# Nusbio_smd.net
KiCad netlist of a schematic drawn in EAGLE
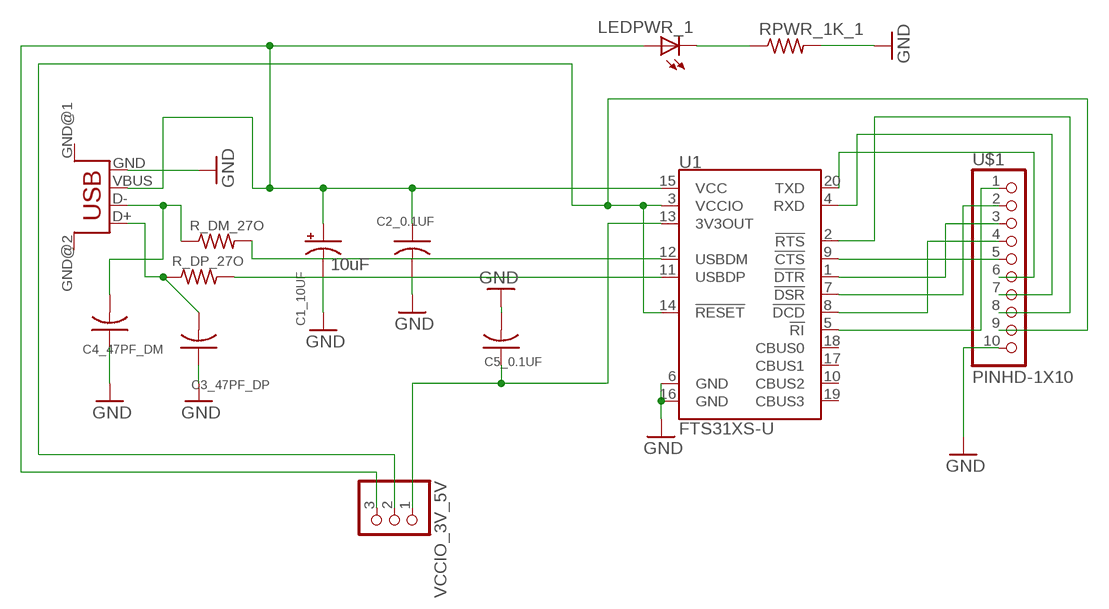
[diagram p0: schematic, sheet 1]

(export (version "E")
  (design (tool "Eeschema 10.0.6"))
  (components
    (comp (ref "C1_10UF")
      (value "10uF")
      (footprint "eagle-import:EIA3216")
      (libsource (lib "eagle-import") (part "10UF-16V-10%(TANT)"))
    )
    (comp (ref "C2_0.1UF")
      (value "C-USC1206")
      (footprint "eagle-import:C1206")
      (libsource (lib "eagle-import") (part "C-USC1206"))
    )
    (comp (ref "C3_47PF_DP")
      (value "C-USC1206")
      (footprint "eagle-import:C1206")
      (libsource (lib "eagle-import") (part "C-USC1206"))
    )
    (comp (ref "C4_47PF_DM")
      (value "C-USC1206")
      (footprint "eagle-import:C1206")
      (libsource (lib "eagle-import") (part "C-USC1206"))
    )
    (comp (ref "C5_0.1UF")
      (value "C-USC1206")
      (footprint "eagle-import:C1206")
      (libsource (lib "eagle-import") (part "C-USC1206"))
    )
    (comp (ref "LEDPWR_1")
      (value "LEDCHIPLED_0805")
      (footprint "eagle-import:CHIPLED_0805")
      (libsource (lib "eagle-import") (part "LEDCHIPLED_0805"))
    )
    (comp (ref "RPWR_1K_1")
      (value "R-US_R0805")
      (footprint "eagle-import:R0805")
      (libsource (lib "eagle-import") (part "R-US_R0805"))
    )
    (comp (ref "R_DM_27O")
      (value "R-US_R0805")
      (footprint "eagle-import:R0805")
      (libsource (lib "eagle-import") (part "R-US_R0805"))
    )
    (comp (ref "R_DP_27O")
      (value "R-US_R0805")
      (footprint "eagle-import:R0805")
      (libsource (lib "eagle-import") (part "R-US_R0805"))
    )
    (comp (ref "U$1")
      (value "PINHD-1X10")
      (footprint "eagle-import:1X10-BIG")
      (libsource (lib "eagle-import") (part "PINHD-1X10"))
    )
    (comp (ref "U1")
      (value "FTS31XS-U")
      (footprint "eagle-import:SSOP20_L")
      (libsource (lib "eagle-import") (part "FT231XS"))
    )
    (comp (ref "USB_FEMALE")
      (value "USB")
      (footprint "eagle-import:USB-FEMALE-A-PTH")
      (libsource (lib "eagle-import") (part "USB"))
    )
    (comp (ref "VCCIO_3V_5V")
      (value "PINHD-1X3")
      (footprint "eagle-import:1X03")
      (libsource (lib "eagle-import") (part "PINHD-1X3"))
    )
  )
  (nets
    (net (code "1") (name "GND") (class "Default")
      (node (ref "C1_10UF") (pin "C") (pinfunction "-_C") (pintype "passive"))
      (node (ref "C2_0.1UF") (pin "2") (pinfunction "2_2") (pintype "passive"))
      (node (ref "C3_47PF_DP") (pin "1") (pinfunction "1_1") (pintype "passive"))
      (node (ref "C4_47PF_DM") (pin "1") (pinfunction "1_1") (pintype "passive"))
      (node (ref "C5_0.1UF") (pin "2") (pinfunction "2_2") (pintype "passive"))
      (node (ref "RPWR_1K_1") (pin "2") (pinfunction "2_2") (pintype "passive"))
      (node (ref "U$1") (pin "10") (pinfunction "10_10") (pintype "passive"))
      (node (ref "U1") (pin "16") (pinfunction "GND_16") (pintype "bidirectional"))
      (node (ref "U1") (pin "6") (pinfunction "GND_6") (pintype "bidirectional"))
      (node (ref "USB_FEMALE") (pin "GND") (pinfunction "GND_GND") (pintype "bidirectional"))
    )
    (net (code "2") (name "Net-(C1_10UF-+)") (class "Default")
      (node (ref "C1_10UF") (pin "A") (pinfunction "+_A") (pintype "passive"))
      (node (ref "C2_0.1UF") (pin "1") (pinfunction "1_1") (pintype "passive"))
      (node (ref "LEDPWR_1") (pin "A") (pinfunction "A_A") (pintype "passive"))
      (node (ref "U1") (pin "15") (pinfunction "VCC_15") (pintype "bidirectional"))
      (node (ref "USB_FEMALE") (pin "VBUS") (pinfunction "VBUS_VBUS") (pintype "bidirectional"))
      (node (ref "VCCIO_3V_5V") (pin "3") (pinfunction "3_3") (pintype "passive"))
    )
    (net (code "3") (name "Net-(C3_47PF_DP-Pad2)") (class "Default")
      (node (ref "C3_47PF_DP") (pin "2") (pinfunction "2_2") (pintype "passive"))
      (node (ref "R_DP_27O") (pin "1") (pinfunction "1_1") (pintype "passive"))
      (node (ref "USB_FEMALE") (pin "D+") (pinfunction "D+_D+") (pintype "bidirectional"))
    )
    (net (code "4") (name "Net-(C4_47PF_DM-Pad2)") (class "Default")
      (node (ref "C4_47PF_DM") (pin "2") (pinfunction "2_2") (pintype "passive"))
      (node (ref "R_DM_27O") (pin "1") (pinfunction "1_1") (pintype "passive"))
      (node (ref "USB_FEMALE") (pin "D-") (pinfunction "D-_D-") (pintype "bidirectional"))
    )
    (net (code "5") (name "Net-(LEDPWR_1-PadC)") (class "Default")
      (node (ref "LEDPWR_1") (pin "C") (pinfunction "C_C") (pintype "passive"))
      (node (ref "RPWR_1K_1") (pin "1") (pinfunction "1_1") (pintype "passive"))
    )
    (net (code "6") (name "Net-(U1-3V3OUT)") (class "Default")
      (node (ref "C5_0.1UF") (pin "1") (pinfunction "1_1") (pintype "passive"))
      (node (ref "U1") (pin "13") (pinfunction "3V3OUT_13") (pintype "bidirectional"))
      (node (ref "VCCIO_3V_5V") (pin "1") (pinfunction "1_1") (pintype "passive"))
    )
    (net (code "7") (name "Net-(U1-RXD)") (class "Default")
      (node (ref "U$1") (pin "7") (pinfunction "7_7") (pintype "passive"))
      (node (ref "U1") (pin "4") (pinfunction "RXD_4") (pintype "bidirectional"))
    )
    (net (code "8") (name "Net-(U1-TXD)") (class "Default")
      (node (ref "U$1") (pin "6") (pinfunction "6_6") (pintype "passive"))
      (node (ref "U1") (pin "20") (pinfunction "TXD_20") (pintype "bidirectional"))
    )
    (net (code "9") (name "Net-(U1-USBDM)") (class "Default")
      (node (ref "R_DM_27O") (pin "2") (pinfunction "2_2") (pintype "passive"))
      (node (ref "U1") (pin "12") (pinfunction "USBDM_12") (pintype "bidirectional"))
    )
    (net (code "10") (name "Net-(U1-USBDP)") (class "Default")
      (node (ref "R_DP_27O") (pin "2") (pinfunction "2_2") (pintype "passive"))
      (node (ref "U1") (pin "11") (pinfunction "USBDP_11") (pintype "bidirectional"))
    )
    (net (code "11") (name "Net-(U1-VCCIO)") (class "Default")
      (node (ref "U$1") (pin "9") (pinfunction "9_9") (pintype "passive"))
      (node (ref "U1") (pin "14") (pinfunction "~{RESET}_14") (pintype "bidirectional"))
      (node (ref "U1") (pin "3") (pinfunction "VCCIO_3") (pintype "bidirectional"))
      (node (ref "VCCIO_3V_5V") (pin "2") (pinfunction "2_2") (pintype "passive"))
    )
    (net (code "12") (name "Net-(U1-~{CTS})") (class "Default")
      (node (ref "U$1") (pin "5") (pinfunction "5_5") (pintype "passive"))
      (node (ref "U1") (pin "9") (pinfunction "~{CTS}_9") (pintype "bidirectional"))
    )
    (net (code "13") (name "Net-(U1-~{DCD})") (class "Default")
      (node (ref "U$1") (pin "4") (pinfunction "4_4") (pintype "passive"))
      (node (ref "U1") (pin "8") (pinfunction "~{DCD}_8") (pintype "bidirectional"))
    )
    (net (code "14") (name "Net-(U1-~{DSR})") (class "Default")
      (node (ref "U$1") (pin "2") (pinfunction "2_2") (pintype "passive"))
      (node (ref "U1") (pin "7") (pinfunction "~{DSR}_7") (pintype "bidirectional"))
    )
    (net (code "15") (name "Net-(U1-~{DTR})") (class "Default")
      (node (ref "U$1") (pin "3") (pinfunction "3_3") (pintype "passive"))
      (node (ref "U1") (pin "1") (pinfunction "~{DTR}_1") (pintype "bidirectional"))
    )
    (net (code "16") (name "Net-(U1-~{RI})") (class "Default")
      (node (ref "U$1") (pin "1") (pinfunction "1_1") (pintype "passive"))
      (node (ref "U1") (pin "5") (pinfunction "~{RI}_5") (pintype "bidirectional"))
    )
    (net (code "17") (name "Net-(U1-~{RTS})") (class "Default")
      (node (ref "U$1") (pin "8") (pinfunction "8_8") (pintype "passive"))
      (node (ref "U1") (pin "2") (pinfunction "~{RTS}_2") (pintype "bidirectional"))
    )
    (net (code "18") (name "unconnected-(U1-CBUS0-Pad18)") (class "Default")
      (node (ref "U1") (pin "18") (pinfunction "CBUS0_18") (pintype "bidirectional"))
    )
    (net (code "19") (name "unconnected-(U1-CBUS1-Pad17)") (class "Default")
      (node (ref "U1") (pin "17") (pinfunction "CBUS1_17") (pintype "bidirectional"))
    )
    (net (code "20") (name "unconnected-(U1-CBUS2-Pad10)") (class "Default")
      (node (ref "U1") (pin "10") (pinfunction "CBUS2_10") (pintype "bidirectional"))
    )
    (net (code "21") (name "unconnected-(U1-CBUS3-Pad19)") (class "Default")
      (node (ref "U1") (pin "19") (pinfunction "CBUS3_19") (pintype "bidirectional"))
    )
    (net (code "22") (name "unconnected-(USB_FEMALE-GND-PadGND@1)") (class "Default")
      (node (ref "USB_FEMALE") (pin "GND@1") (pinfunction "GND_GND@1") (pintype "bidirectional"))
    )
    (net (code "23") (name "unconnected-(USB_FEMALE-GND-PadGND@2)") (class "Default")
      (node (ref "USB_FEMALE") (pin "GND@2") (pinfunction "GND_GND@2") (pintype "bidirectional"))
    )
  )
)
